# schematics.net
KiCad netlist of a schematic drawn in EAGLE
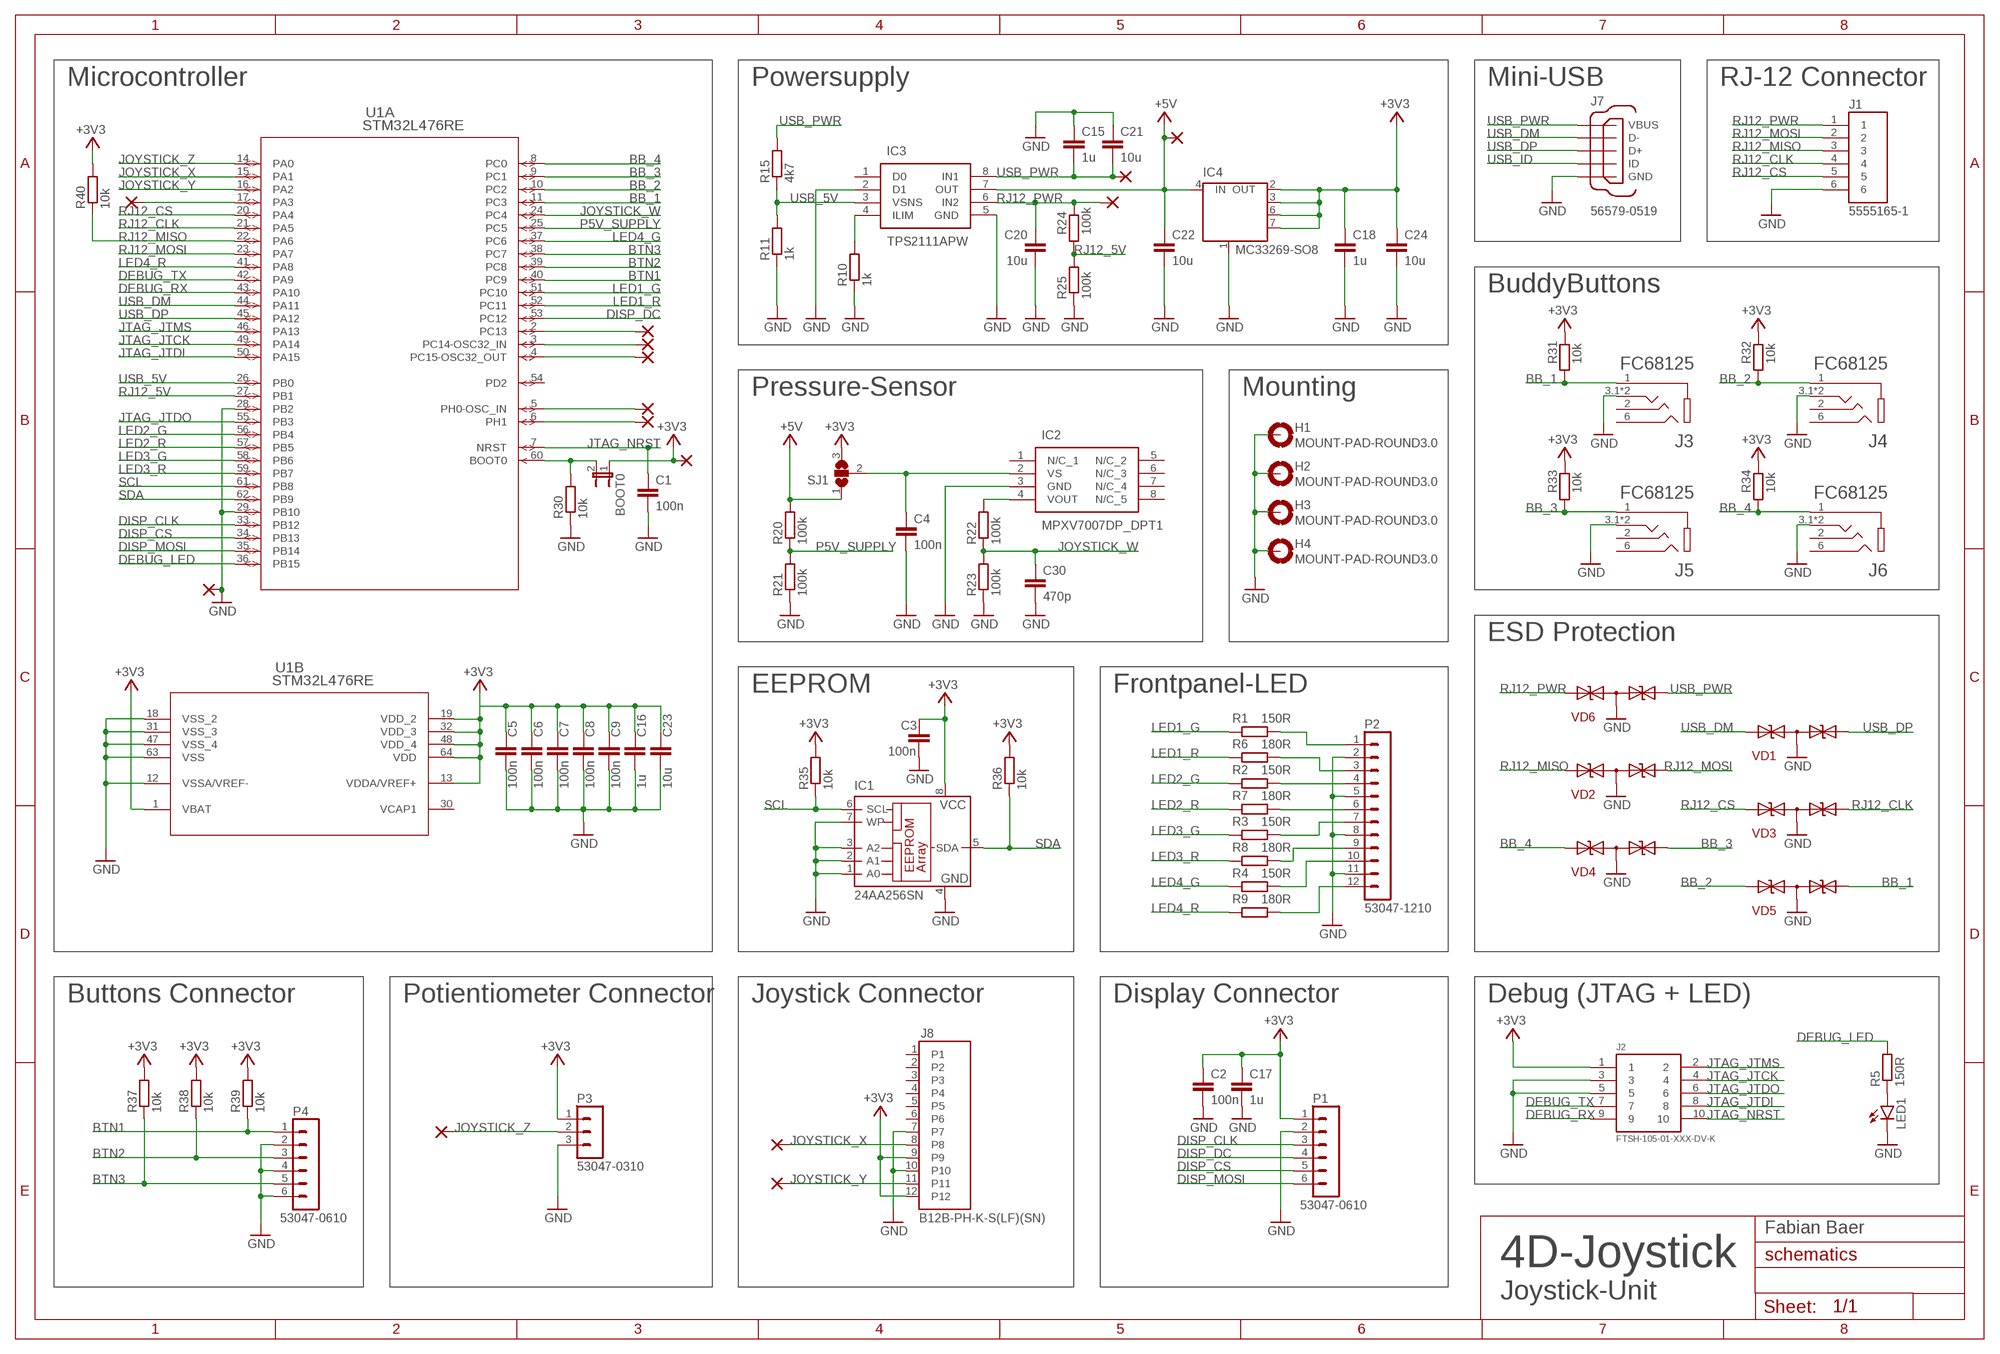
[diagram p0: schematic, sheet 1]

(export (version "E")
  (design (tool "Eeschema 10.0.6"))
  (components
    (comp (ref "BOOT0")
      (value "JP1E")
      (footprint "eagle-import:JP1")
      (libsource (lib "eagle-import") (part "JP1E"))
    )
    (comp (ref "C1")
      (value "100n")
      (footprint "eagle-import:C0603")
      (libsource (lib "eagle-import") (part "C-EUC0603"))
    )
    (comp (ref "C2")
      (value "100n")
      (footprint "eagle-import:C0603")
      (libsource (lib "eagle-import") (part "C-EUC0603"))
    )
    (comp (ref "C3")
      (value "100n")
      (footprint "eagle-import:C0603")
      (libsource (lib "eagle-import") (part "C-EUC0603"))
    )
    (comp (ref "C4")
      (value "100n")
      (footprint "eagle-import:C0603")
      (libsource (lib "eagle-import") (part "C-EUC0603"))
    )
    (comp (ref "C5")
      (value "100n")
      (footprint "eagle-import:C0603")
      (libsource (lib "eagle-import") (part "C-EUC0603"))
    )
    (comp (ref "C6")
      (value "100n")
      (footprint "eagle-import:C0603")
      (libsource (lib "eagle-import") (part "C-EUC0603"))
    )
    (comp (ref "C7")
      (value "100n")
      (footprint "eagle-import:C0603")
      (libsource (lib "eagle-import") (part "C-EUC0603"))
    )
    (comp (ref "C8")
      (value "100n")
      (footprint "eagle-import:C0603")
      (libsource (lib "eagle-import") (part "C-EUC0603"))
    )
    (comp (ref "C9")
      (value "100n")
      (footprint "eagle-import:C0603")
      (libsource (lib "eagle-import") (part "C-EUC0603"))
    )
    (comp (ref "C15")
      (value "1u")
      (footprint "eagle-import:C0603")
      (libsource (lib "eagle-import") (part "C-EUC0603"))
    )
    (comp (ref "C16")
      (value "1u")
      (footprint "eagle-import:C0603")
      (libsource (lib "eagle-import") (part "C-EUC0603"))
    )
    (comp (ref "C17")
      (value "1u")
      (footprint "eagle-import:C0603")
      (libsource (lib "eagle-import") (part "C-EUC0603"))
    )
    (comp (ref "C18")
      (value "1u")
      (footprint "eagle-import:C0603")
      (libsource (lib "eagle-import") (part "C-EUC0603"))
    )
    (comp (ref "C20")
      (value "10u")
      (footprint "eagle-import:C0603")
      (libsource (lib "eagle-import") (part "C-EUC0603"))
    )
    (comp (ref "C21")
      (value "10u")
      (footprint "eagle-import:C0603")
      (libsource (lib "eagle-import") (part "C-EUC0603"))
    )
    (comp (ref "C22")
      (value "10u")
      (footprint "eagle-import:C0603")
      (libsource (lib "eagle-import") (part "C-EUC0603"))
    )
    (comp (ref "C23")
      (value "10u")
      (footprint "eagle-import:C0603")
      (libsource (lib "eagle-import") (part "C-EUC0603"))
    )
    (comp (ref "C24")
      (value "10u")
      (footprint "eagle-import:C0603")
      (libsource (lib "eagle-import") (part "C-EUC0603"))
    )
    (comp (ref "C30")
      (value "470p")
      (footprint "eagle-import:C0603")
      (libsource (lib "eagle-import") (part "C-EUC0603"))
    )
    (comp (ref "H1")
      (value "MOUNT-PAD-ROUND3.0")
      (footprint "eagle-import:3,0-PAD")
      (libsource (lib "eagle-import") (part "MOUNT-PAD-ROUND3.0"))
    )
    (comp (ref "H2")
      (value "MOUNT-PAD-ROUND3.0")
      (footprint "eagle-import:3,0-PAD")
      (libsource (lib "eagle-import") (part "MOUNT-PAD-ROUND3.0"))
    )
    (comp (ref "H3")
      (value "MOUNT-PAD-ROUND3.0")
      (footprint "eagle-import:3,0-PAD")
      (libsource (lib "eagle-import") (part "MOUNT-PAD-ROUND3.0"))
    )
    (comp (ref "H4")
      (value "MOUNT-PAD-ROUND3.0")
      (footprint "eagle-import:3,0-PAD")
      (libsource (lib "eagle-import") (part "MOUNT-PAD-ROUND3.0"))
    )
    (comp (ref "IC1")
      (value "24AA256SN")
      (footprint "eagle-import:SO-08")
      (fields (field (name "MPN") "24AA256T-I/SM"))
      (libsource (lib "eagle-import") (part "24SNAA256"))
    )
    (comp (ref "IC2")
      (value "MPXV7007DP_DPT1")
      (footprint "eagle-import:MPXV7007DPDPT1")
      (fields (field (name "MANUFACTURER_PART_NUMBER") "MPXV7007DP/DPT1"))
      (libsource (lib "eagle-import") (part "MPXV7007DP_DPT1"))
    )
    (comp (ref "IC3")
      (value "TPS2111APW")
      (footprint "eagle-import:SOP65P640X120-8N")
      (fields (field (name "MOUSER_PART_NUMBER") "595-TPS2111APW") (field (name "RS_PART_NUMBER") "6658866P"))
      (libsource (lib "eagle-import") (part "TPS2111APW"))
    )
    (comp (ref "IC4")
      (value "MC33269-SO8")
      (footprint "eagle-import:SO08")
      (libsource (lib "eagle-import") (part "MC33269-SO8"))
    )
    (comp (ref "J1")
      (value "5555165-1")
      (footprint "eagle-import:TE_5555165-1")
      (fields (field (name "MF") "TE Connectivity"))
      (libsource (lib "eagle-import") (part "5555165-1"))
    )
    (comp (ref "J2")
      (value "FTSH-105-01-XXX-DV-K")
      (footprint "eagle-import:FTSH-105-01-XXX-DV-K")
      (libsource (lib "eagle-import") (part "FTSH-105-01-XXX-DV-K"))
    )
    (comp (ref "J3")
      (value "FC68125")
      (footprint "eagle-import:CLIFF_FC68125")
      (fields (field (name "MF") "Cliff Electronics"))
      (libsource (lib "eagle-import") (part "FC68125"))
    )
    (comp (ref "J4")
      (value "FC68125")
      (footprint "eagle-import:CLIFF_FC68125")
      (fields (field (name "MF") "Cliff Electronics"))
      (libsource (lib "eagle-import") (part "FC68125"))
    )
    (comp (ref "J5")
      (value "FC68125")
      (footprint "eagle-import:CLIFF_FC68125")
      (fields (field (name "MF") "Cliff Electronics"))
      (libsource (lib "eagle-import") (part "FC68125"))
    )
    (comp (ref "J6")
      (value "FC68125")
      (footprint "eagle-import:CLIFF_FC68125")
      (fields (field (name "MF") "Cliff Electronics"))
      (libsource (lib "eagle-import") (part "FC68125"))
    )
    (comp (ref "J7")
      (value "56579-0519")
      (footprint "eagle-import:MOLEX_56579-0519")
      (fields (field (name "MF") "Molex"))
      (libsource (lib "eagle-import") (part "56579-0519"))
    )
    (comp (ref "J8")
      (value "B12B-PH-K-S(LF)(SN)")
      (footprint "eagle-import:JST_B12B-PH-K-S(LF)(SN)")
      (fields (field (name "MF") "JST Sales") (field (name "MP") "B12B-PH-K-S_LF__SN_"))
      (libsource (lib "eagle-import") (part "B12B-PH-K-S(LF)(SN)"))
    )
    (comp (ref "LED1")
      (value "LEDSML0603")
      (footprint "eagle-import:SML0603")
      (libsource (lib "eagle-import") (part "LEDSML0603"))
    )
    (comp (ref "P1")
      (value "53047-0610")
      (footprint "eagle-import:53047-0610")
      (libsource (lib "eagle-import") (part "53047-0610"))
    )
    (comp (ref "P2")
      (value "53047-1210")
      (footprint "eagle-import:53047-1210")
      (libsource (lib "eagle-import") (part "53047-1210"))
    )
    (comp (ref "P3")
      (value "53047-0310")
      (footprint "eagle-import:53047-0310")
      (libsource (lib "eagle-import") (part "53047-0310"))
    )
    (comp (ref "P4")
      (value "53047-0610")
      (footprint "eagle-import:53047-0610")
      (libsource (lib "eagle-import") (part "53047-0610"))
    )
    (comp (ref "PAD1")
      (value "WIREPAD1,6/0,9")
      (footprint "eagle-import:1,6_0,9")
      (libsource (lib "eagle-import") (part "WIREPAD1,6/0,9"))
    )
    (comp (ref "PAD2")
      (value "WIREPAD1,6/0,9")
      (footprint "eagle-import:1,6_0,9")
      (libsource (lib "eagle-import") (part "WIREPAD1,6/0,9"))
    )
    (comp (ref "PAD3")
      (value "WIREPAD1,6/0,9")
      (footprint "eagle-import:1,6_0,9")
      (libsource (lib "eagle-import") (part "WIREPAD1,6/0,9"))
    )
    (comp (ref "PAD4")
      (value "WIREPAD1,6/0,9")
      (footprint "eagle-import:1,6_0,9")
      (libsource (lib "eagle-import") (part "WIREPAD1,6/0,9"))
    )
    (comp (ref "PAD5")
      (value "WIREPAD1,6/0,9")
      (footprint "eagle-import:1,6_0,9")
      (libsource (lib "eagle-import") (part "WIREPAD1,6/0,9"))
    )
    (comp (ref "PAD6")
      (value "WIREPAD1,6/0,9")
      (footprint "eagle-import:1,6_0,9")
      (libsource (lib "eagle-import") (part "WIREPAD1,6/0,9"))
    )
    (comp (ref "PAD7")
      (value "WIREPAD1,6/0,9")
      (footprint "eagle-import:1,6_0,9")
      (libsource (lib "eagle-import") (part "WIREPAD1,6/0,9"))
    )
    (comp (ref "PAD8")
      (value "WIREPAD1,6/0,9")
      (footprint "eagle-import:1,6_0,9")
      (libsource (lib "eagle-import") (part "WIREPAD1,6/0,9"))
    )
    (comp (ref "PAD9")
      (value "WIREPAD1,6/0,9")
      (footprint "eagle-import:1,6_0,9")
      (libsource (lib "eagle-import") (part "WIREPAD1,6/0,9"))
    )
    (comp (ref "PAD10")
      (value "WIREPAD1,6/0,9")
      (footprint "eagle-import:1,6_0,9")
      (libsource (lib "eagle-import") (part "WIREPAD1,6/0,9"))
    )
    (comp (ref "PAD11")
      (value "WIREPAD1,6/0,9")
      (footprint "eagle-import:1,6_0,9")
      (libsource (lib "eagle-import") (part "WIREPAD1,6/0,9"))
    )
    (comp (ref "PAD12")
      (value "WIREPAD1,6/0,9")
      (footprint "eagle-import:1,6_0,9")
      (libsource (lib "eagle-import") (part "WIREPAD1,6/0,9"))
    )
    (comp (ref "PAD13")
      (value "WIREPAD1,6/0,9")
      (footprint "eagle-import:1,6_0,9")
      (libsource (lib "eagle-import") (part "WIREPAD1,6/0,9"))
    )
    (comp (ref "PAD14")
      (value "WIREPAD1,6/0,9")
      (footprint "eagle-import:1,6_0,9")
      (libsource (lib "eagle-import") (part "WIREPAD1,6/0,9"))
    )
    (comp (ref "R1")
      (value "150R")
      (footprint "eagle-import:R0603")
      (libsource (lib "eagle-import") (part "R-EU_R0603"))
    )
    (comp (ref "R2")
      (value "150R")
      (footprint "eagle-import:R0603")
      (libsource (lib "eagle-import") (part "R-EU_R0603"))
    )
    (comp (ref "R3")
      (value "150R")
      (footprint "eagle-import:R0603")
      (libsource (lib "eagle-import") (part "R-EU_R0603"))
    )
    (comp (ref "R4")
      (value "150R")
      (footprint "eagle-import:R0603")
      (libsource (lib "eagle-import") (part "R-EU_R0603"))
    )
    (comp (ref "R5")
      (value "150R")
      (footprint "eagle-import:R0603")
      (libsource (lib "eagle-import") (part "R-EU_R0603"))
    )
    (comp (ref "R6")
      (value "180R")
      (footprint "eagle-import:R0603")
      (libsource (lib "eagle-import") (part "R-EU_R0603"))
    )
    (comp (ref "R7")
      (value "180R")
      (footprint "eagle-import:R0603")
      (libsource (lib "eagle-import") (part "R-EU_R0603"))
    )
    (comp (ref "R8")
      (value "180R")
      (footprint "eagle-import:R0603")
      (libsource (lib "eagle-import") (part "R-EU_R0603"))
    )
    (comp (ref "R9")
      (value "180R")
      (footprint "eagle-import:R0603")
      (libsource (lib "eagle-import") (part "R-EU_R0603"))
    )
    (comp (ref "R10")
      (value "1k")
      (footprint "eagle-import:R0603")
      (libsource (lib "eagle-import") (part "R-EU_R0603"))
    )
    (comp (ref "R11")
      (value "1k")
      (footprint "eagle-import:R0603")
      (libsource (lib "eagle-import") (part "R-EU_R0603"))
    )
    (comp (ref "R15")
      (value "4k7")
      (footprint "eagle-import:R0603")
      (libsource (lib "eagle-import") (part "R-EU_R0603"))
    )
    (comp (ref "R20")
      (value "100k")
      (footprint "eagle-import:R0603")
      (libsource (lib "eagle-import") (part "R-EU_R0603"))
    )
    (comp (ref "R21")
      (value "100k")
      (footprint "eagle-import:R0603")
      (libsource (lib "eagle-import") (part "R-EU_R0603"))
    )
    (comp (ref "R22")
      (value "100k")
      (footprint "eagle-import:R0603")
      (libsource (lib "eagle-import") (part "R-EU_R0603"))
    )
    (comp (ref "R23")
      (value "100k")
      (footprint "eagle-import:R0603")
      (libsource (lib "eagle-import") (part "R-EU_R0603"))
    )
    (comp (ref "R24")
      (value "100k")
      (footprint "eagle-import:R0603")
      (libsource (lib "eagle-import") (part "R-EU_R0603"))
    )
    (comp (ref "R25")
      (value "100k")
      (footprint "eagle-import:R0603")
      (libsource (lib "eagle-import") (part "R-EU_R0603"))
    )
    (comp (ref "R30")
      (value "10k")
      (footprint "eagle-import:R0603")
      (libsource (lib "eagle-import") (part "R-EU_R0603"))
    )
    (comp (ref "R31")
      (value "10k")
      (footprint "eagle-import:R0603")
      (libsource (lib "eagle-import") (part "R-EU_R0603"))
    )
    (comp (ref "R32")
      (value "10k")
      (footprint "eagle-import:R0603")
      (libsource (lib "eagle-import") (part "R-EU_R0603"))
    )
    (comp (ref "R33")
      (value "10k")
      (footprint "eagle-import:R0603")
      (libsource (lib "eagle-import") (part "R-EU_R0603"))
    )
    (comp (ref "R34")
      (value "10k")
      (footprint "eagle-import:R0603")
      (libsource (lib "eagle-import") (part "R-EU_R0603"))
    )
    (comp (ref "R35")
      (value "10k")
      (footprint "eagle-import:R0603")
      (libsource (lib "eagle-import") (part "R-EU_R0603"))
    )
    (comp (ref "R36")
      (value "10k")
      (footprint "eagle-import:R0603")
      (libsource (lib "eagle-import") (part "R-EU_R0603"))
    )
    (comp (ref "R37")
      (value "10k")
      (footprint "eagle-import:R0603")
      (libsource (lib "eagle-import") (part "R-EU_R0603"))
    )
    (comp (ref "R38")
      (value "10k")
      (footprint "eagle-import:R0603")
      (libsource (lib "eagle-import") (part "R-EU_R0603"))
    )
    (comp (ref "R39")
      (value "10k")
      (footprint "eagle-import:R0603")
      (libsource (lib "eagle-import") (part "R-EU_R0603"))
    )
    (comp (ref "R40")
      (value "10k")
      (footprint "eagle-import:R0603")
      (libsource (lib "eagle-import") (part "R-EU_R0603"))
    )
    (comp (ref "SJ1")
      (value "SJ2W")
      (footprint "eagle-import:SJ_2")
      (libsource (lib "eagle-import") (part "SJ2W"))
    )
    (comp (ref "U1")
      (value "STM32L476RE")
      (footprint "eagle-import:LQFP64-10X10MM")
      (fields (field (name "MANUFACTURER_PART_NUMBER") "STM32F4X1R1"))
      (libsource (lib "eagle-import") (part "STM32F4X1R1"))
    )
    (comp (ref "VD1")
      (value "PGB102ST23WR")
      (footprint "eagle-import:SOT23")
      (libsource (lib "eagle-import") (part "PGB102ST23WR"))
    )
    (comp (ref "VD2")
      (value "PGB102ST23WR")
      (footprint "eagle-import:SOT23")
      (libsource (lib "eagle-import") (part "PGB102ST23WR"))
    )
    (comp (ref "VD3")
      (value "PGB102ST23WR")
      (footprint "eagle-import:SOT23")
      (libsource (lib "eagle-import") (part "PGB102ST23WR"))
    )
    (comp (ref "VD4")
      (value "PGB102ST23WR")
      (footprint "eagle-import:SOT23")
      (libsource (lib "eagle-import") (part "PGB102ST23WR"))
    )
    (comp (ref "VD5")
      (value "PGB102ST23WR")
      (footprint "eagle-import:SOT23")
      (libsource (lib "eagle-import") (part "PGB102ST23WR"))
    )
    (comp (ref "VD6")
      (value "PGB102ST23WR")
      (footprint "eagle-import:SOT23")
      (libsource (lib "eagle-import") (part "PGB102ST23WR"))
    )
  )
  (nets
    (net (code "1") (name "+3V3") (class "Default")
      (node (ref "BOOT0") (pin "1") (pinfunction "1_1") (pintype "passive"))
      (node (ref "C16") (pin "1") (pinfunction "1_1") (pintype "passive"))
      (node (ref "C17") (pin "1") (pinfunction "1_1") (pintype "passive"))
      (node (ref "C18") (pin "1") (pinfunction "1_1") (pintype "passive"))
      (node (ref "C2") (pin "1") (pinfunction "1_1") (pintype "passive"))
      (node (ref "C23") (pin "1") (pinfunction "1_1") (pintype "passive"))
      (node (ref "C24") (pin "1") (pinfunction "1_1") (pintype "passive"))
      (node (ref "C3") (pin "1") (pinfunction "1_1") (pintype "passive"))
      (node (ref "C5") (pin "1") (pinfunction "1_1") (pintype "passive"))
      (node (ref "C6") (pin "1") (pinfunction "1_1") (pintype "passive"))
      (node (ref "C7") (pin "1") (pinfunction "1_1") (pintype "passive"))
      (node (ref "C8") (pin "1") (pinfunction "1_1") (pintype "passive"))
      (node (ref "C9") (pin "1") (pinfunction "1_1") (pintype "passive"))
      (node (ref "IC1") (pin "8") (pinfunction "VCC_8") (pintype "power_in"))
      (node (ref "IC4") (pin "2") (pinfunction "OUT_2") (pintype "passive"))
      (node (ref "IC4") (pin "3") (pinfunction "OUT_3") (pintype "passive"))
      (node (ref "IC4") (pin "6") (pinfunction "OUT_6") (pintype "passive"))
      (node (ref "IC4") (pin "7") (pinfunction "OUT_7") (pintype "passive"))
      (node (ref "J2") (pin "1") (pinfunction "1_1") (pintype "bidirectional"))
      (node (ref "J8") (pin "12") (pinfunction "P12_12") (pintype "passive"))
      (node (ref "J8") (pin "9") (pinfunction "P9_9") (pintype "passive"))
      (node (ref "P1") (pin "1") (pinfunction "1_1") (pintype "passive"))
      (node (ref "P3") (pin "1") (pinfunction "1_1") (pintype "passive"))
      (node (ref "PAD7") (pin "1") (pinfunction "P_1") (pintype "passive"))
      (node (ref "R31") (pin "2") (pinfunction "2_2") (pintype "passive"))
      (node (ref "R32") (pin "2") (pinfunction "2_2") (pintype "passive"))
      (node (ref "R33") (pin "2") (pinfunction "2_2") (pintype "passive"))
      (node (ref "R34") (pin "2") (pinfunction "2_2") (pintype "passive"))
      (node (ref "R35") (pin "2") (pinfunction "2_2") (pintype "passive"))
      (node (ref "R36") (pin "2") (pinfunction "2_2") (pintype "passive"))
      (node (ref "R37") (pin "2") (pinfunction "2_2") (pintype "passive"))
      (node (ref "R38") (pin "2") (pinfunction "2_2") (pintype "passive"))
      (node (ref "R39") (pin "2") (pinfunction "2_2") (pintype "passive"))
      (node (ref "R40") (pin "2") (pinfunction "2_2") (pintype "passive"))
      (node (ref "SJ1") (pin "3") (pinfunction "3_3") (pintype "passive"))
      (node (ref "U1") (pin "1") (pinfunction "VBAT_1") (pintype "power_in"))
      (node (ref "U1") (pin "13") (pinfunction "VDDA/VREF+_13") (pintype "power_in"))
      (node (ref "U1") (pin "19") (pinfunction "VDD_2_19") (pintype "power_in"))
      (node (ref "U1") (pin "32") (pinfunction "VDD_3_32") (pintype "power_in"))
      (node (ref "U1") (pin "48") (pinfunction "VDD_4_48") (pintype "power_in"))
      (node (ref "U1") (pin "64") (pinfunction "VDD_64") (pintype "power_in"))
    )
    (net (code "2") (name "+5V") (class "Default")
      (node (ref "C22") (pin "1") (pinfunction "1_1") (pintype "passive"))
      (node (ref "IC3") (pin "7") (pinfunction "OUT_7") (pintype "output"))
      (node (ref "IC4") (pin "4") (pinfunction "IN_4") (pintype "input"))
      (node (ref "PAD9") (pin "1") (pinfunction "P_1") (pintype "passive"))
      (node (ref "R20") (pin "2") (pinfunction "2_2") (pintype "passive"))
      (node (ref "SJ1") (pin "1") (pinfunction "1_1") (pintype "passive"))
    )
    (net (code "3") (name "/BB_1") (class "Default")
      (node (ref "J3") (pin "1") (pinfunction "1S_1") (pintype "passive"))
      (node (ref "R31") (pin "1") (pinfunction "1_1") (pintype "passive"))
      (node (ref "U1") (pin "11") (pinfunction "PC3_11") (pintype "bidirectional"))
      (node (ref "VD5") (pin "1") (pinfunction "A_1") (pintype "passive"))
    )
    (net (code "4") (name "/BB_2") (class "Default")
      (node (ref "J4") (pin "1") (pinfunction "1S_1") (pintype "passive"))
      (node (ref "R32") (pin "1") (pinfunction "1_1") (pintype "passive"))
      (node (ref "U1") (pin "10") (pinfunction "PC2_10") (pintype "bidirectional"))
      (node (ref "VD5") (pin "2") (pinfunction "A1_2") (pintype "passive"))
    )
    (net (code "5") (name "/BB_3") (class "Default")
      (node (ref "J5") (pin "1") (pinfunction "1S_1") (pintype "passive"))
      (node (ref "R33") (pin "1") (pinfunction "1_1") (pintype "passive"))
      (node (ref "U1") (pin "9") (pinfunction "PC1_9") (pintype "bidirectional"))
      (node (ref "VD4") (pin "1") (pinfunction "A_1") (pintype "passive"))
    )
    (net (code "6") (name "/BB_4") (class "Default")
      (node (ref "J6") (pin "1") (pinfunction "1S_1") (pintype "passive"))
      (node (ref "R34") (pin "1") (pinfunction "1_1") (pintype "passive"))
      (node (ref "U1") (pin "8") (pinfunction "PC0_8") (pintype "bidirectional"))
      (node (ref "VD4") (pin "2") (pinfunction "A1_2") (pintype "passive"))
    )
    (net (code "7") (name "/BTN1") (class "Default")
      (node (ref "P4") (pin "1") (pinfunction "1_1") (pintype "passive"))
      (node (ref "R39") (pin "1") (pinfunction "1_1") (pintype "passive"))
      (node (ref "U1") (pin "40") (pinfunction "PC9_40") (pintype "bidirectional"))
    )
    (net (code "8") (name "/BTN2") (class "Default")
      (node (ref "P4") (pin "3") (pinfunction "3_3") (pintype "passive"))
      (node (ref "R38") (pin "1") (pinfunction "1_1") (pintype "passive"))
      (node (ref "U1") (pin "39") (pinfunction "PC8_39") (pintype "bidirectional"))
    )
    (net (code "9") (name "/BTN3") (class "Default")
      (node (ref "P4") (pin "5") (pinfunction "5_5") (pintype "passive"))
      (node (ref "R37") (pin "1") (pinfunction "1_1") (pintype "passive"))
      (node (ref "U1") (pin "38") (pinfunction "PC7_38") (pintype "bidirectional"))
    )
    (net (code "10") (name "/DEBUG_LED") (class "Default")
      (node (ref "R5") (pin "2") (pinfunction "2_2") (pintype "passive"))
      (node (ref "U1") (pin "36") (pinfunction "PB15_36") (pintype "bidirectional"))
    )
    (net (code "11") (name "/DEBUG_RX") (class "Default")
      (node (ref "J2") (pin "9") (pinfunction "9_9") (pintype "bidirectional"))
      (node (ref "U1") (pin "43") (pinfunction "PA10_43") (pintype "bidirectional"))
    )
    (net (code "12") (name "/DEBUG_TX") (class "Default")
      (node (ref "J2") (pin "7") (pinfunction "7_7") (pintype "bidirectional"))
      (node (ref "U1") (pin "42") (pinfunction "PA9_42") (pintype "bidirectional"))
    )
    (net (code "13") (name "/DISP_CLK") (class "Default")
      (node (ref "P1") (pin "3") (pinfunction "3_3") (pintype "passive"))
      (node (ref "U1") (pin "33") (pinfunction "PB12_33") (pintype "bidirectional"))
    )
    (net (code "14") (name "/DISP_CS") (class "Default")
      (node (ref "P1") (pin "5") (pinfunction "5_5") (pintype "passive"))
      (node (ref "U1") (pin "34") (pinfunction "PB13_34") (pintype "bidirectional"))
    )
    (net (code "15") (name "/DISP_DC") (class "Default")
      (node (ref "P1") (pin "4") (pinfunction "4_4") (pintype "passive"))
      (node (ref "U1") (pin "53") (pinfunction "PC12_53") (pintype "bidirectional"))
    )
    (net (code "16") (name "/DISP_MOSI") (class "Default")
      (node (ref "P1") (pin "6") (pinfunction "6_6") (pintype "passive"))
      (node (ref "U1") (pin "35") (pinfunction "PB14_35") (pintype "bidirectional"))
    )
    (net (code "17") (name "/JOYSTICK_W") (class "Default")
      (node (ref "C30") (pin "1") (pinfunction "1_1") (pintype "passive"))
      (node (ref "R22") (pin "1") (pinfunction "1_1") (pintype "passive"))
      (node (ref "R23") (pin "2") (pinfunction "2_2") (pintype "passive"))
      (node (ref "U1") (pin "24") (pinfunction "PC4_24") (pintype "bidirectional"))
    )
    (net (code "18") (name "/JOYSTICK_X") (class "Default")
      (node (ref "J8") (pin "8") (pinfunction "P8_8") (pintype "passive"))
      (node (ref "PAD12") (pin "1") (pinfunction "P_1") (pintype "passive"))
      (node (ref "U1") (pin "15") (pinfunction "PA1_15") (pintype "bidirectional"))
    )
    (net (code "19") (name "/JOYSTICK_Y") (class "Default")
      (node (ref "J8") (pin "11") (pinfunction "P11_11") (pintype "passive"))
      (node (ref "PAD13") (pin "1") (pinfunction "P_1") (pintype "passive"))
      (node (ref "U1") (pin "16") (pinfunction "PA2_16") (pintype "bidirectional"))
    )
    (net (code "20") (name "/JOYSTICK_Z") (class "Default")
      (node (ref "P3") (pin "2") (pinfunction "2_2") (pintype "passive"))
      (node (ref "PAD14") (pin "1") (pinfunction "P_1") (pintype "passive"))
      (node (ref "U1") (pin "14") (pinfunction "PA0_14") (pintype "bidirectional"))
    )
    (net (code "21") (name "/JTAG_JTCK") (class "Default")
      (node (ref "J2") (pin "4") (pinfunction "4_4") (pintype "bidirectional"))
      (node (ref "U1") (pin "49") (pinfunction "PA14_49") (pintype "bidirectional"))
    )
    (net (code "22") (name "/JTAG_JTDI") (class "Default")
      (node (ref "J2") (pin "8") (pinfunction "8_8") (pintype "bidirectional"))
      (node (ref "U1") (pin "50") (pinfunction "PA15_50") (pintype "bidirectional"))
    )
    (net (code "23") (name "/JTAG_JTDO") (class "Default")
      (node (ref "J2") (pin "6") (pinfunction "6_6") (pintype "bidirectional"))
      (node (ref "U1") (pin "55") (pinfunction "PB3_55") (pintype "bidirectional"))
    )
    (net (code "24") (name "/JTAG_JTMS") (class "Default")
      (node (ref "J2") (pin "2") (pinfunction "2_2") (pintype "bidirectional"))
      (node (ref "U1") (pin "46") (pinfunction "PA13_46") (pintype "bidirectional"))
    )
    (net (code "25") (name "/JTAG_NRST") (class "Default")
      (node (ref "C1") (pin "1") (pinfunction "1_1") (pintype "passive"))
      (node (ref "J2") (pin "10") (pinfunction "10_10") (pintype "bidirectional"))
      (node (ref "U1") (pin "7") (pinfunction "NRST_7") (pintype "bidirectional"))
    )
    (net (code "26") (name "/LED1_G") (class "Default")
      (node (ref "R1") (pin "2") (pinfunction "2_2") (pintype "passive"))
      (node (ref "U1") (pin "51") (pinfunction "PC10_51") (pintype "bidirectional"))
    )
    (net (code "27") (name "/LED1_R") (class "Default")
      (node (ref "R6") (pin "2") (pinfunction "2_2") (pintype "passive"))
      (node (ref "U1") (pin "52") (pinfunction "PC11_52") (pintype "bidirectional"))
    )
    (net (code "28") (name "/LED2_G") (class "Default")
      (node (ref "R2") (pin "2") (pinfunction "2_2") (pintype "passive"))
      (node (ref "U1") (pin "56") (pinfunction "PB4_56") (pintype "bidirectional"))
    )
    (net (code "29") (name "/LED2_R") (class "Default")
      (node (ref "R7") (pin "2") (pinfunction "2_2") (pintype "passive"))
      (node (ref "U1") (pin "57") (pinfunction "PB5_57") (pintype "bidirectional"))
    )
    (net (code "30") (name "/LED3_G") (class "Default")
      (node (ref "R3") (pin "2") (pinfunction "2_2") (pintype "passive"))
      (node (ref "U1") (pin "58") (pinfunction "PB6_58") (pintype "bidirectional"))
    )
    (net (code "31") (name "/LED3_R") (class "Default")
      (node (ref "R8") (pin "2") (pinfunction "2_2") (pintype "passive"))
      (node (ref "U1") (pin "59") (pinfunction "PB7_59") (pintype "bidirectional"))
    )
    (net (code "32") (name "/LED4_G") (class "Default")
      (node (ref "R4") (pin "2") (pinfunction "2_2") (pintype "passive"))
      (node (ref "U1") (pin "37") (pinfunction "PC6_37") (pintype "bidirectional"))
    )
    (net (code "33") (name "/LED4_R") (class "Default")
      (node (ref "R9") (pin "2") (pinfunction "2_2") (pintype "passive"))
      (node (ref "U1") (pin "41") (pinfunction "PA8_41") (pintype "bidirectional"))
    )
    (net (code "34") (name "/P5V_SUPPLY") (class "Default")
      (node (ref "R20") (pin "1") (pinfunction "1_1") (pintype "passive"))
      (node (ref "R21") (pin "2") (pinfunction "2_2") (pintype "passive"))
      (node (ref "U1") (pin "25") (pinfunction "PC5_25") (pintype "bidirectional"))
    )
    (net (code "35") (name "/RJ12_5V") (class "Default")
      (node (ref "R24") (pin "1") (pinfunction "1_1") (pintype "passive"))
      (node (ref "R25") (pin "2") (pinfunction "2_2") (pintype "passive"))
      (node (ref "U1") (pin "27") (pinfunction "PB1_27") (pintype "bidirectional"))
    )
    (net (code "36") (name "/RJ12_CLK") (class "Default")
      (node (ref "J1") (pin "4") (pinfunction "4_4") (pintype "passive"))
      (node (ref "U1") (pin "21") (pinfunction "PA5_21") (pintype "bidirectional"))
      (node (ref "VD3") (pin "1") (pinfunction "A_1") (pintype "passive"))
    )
    (net (code "37") (name "/RJ12_CS") (class "Default")
      (node (ref "J1") (pin "5") (pinfunction "5_5") (pintype "passive"))
      (node (ref "U1") (pin "20") (pinfunction "PA4_20") (pintype "bidirectional"))
      (node (ref "VD3") (pin "2") (pinfunction "A1_2") (pintype "passive"))
    )
    (net (code "38") (name "/RJ12_MISO") (class "Default")
      (node (ref "J1") (pin "3") (pinfunction "3_3") (pintype "passive"))
      (node (ref "R40") (pin "1") (pinfunction "1_1") (pintype "passive"))
      (node (ref "U1") (pin "22") (pinfunction "PA6_22") (pintype "bidirectional"))
      (node (ref "VD2") (pin "2") (pinfunction "A1_2") (pintype "passive"))
    )
    (net (code "39") (name "/RJ12_MOSI") (class "Default")
      (node (ref "J1") (pin "2") (pinfunction "2_2") (pintype "passive"))
      (node (ref "U1") (pin "23") (pinfunction "PA7_23") (pintype "bidirectional"))
      (node (ref "VD2") (pin "1") (pinfunction "A_1") (pintype "passive"))
    )
    (net (code "40") (name "/RJ12_PWR") (class "Default")
      (node (ref "C20") (pin "1") (pinfunction "1_1") (pintype "passive"))
      (node (ref "IC3") (pin "6") (pinfunction "IN2_6") (pintype "input"))
      (node (ref "J1") (pin "1") (pinfunction "1_1") (pintype "passive"))
      (node (ref "PAD11") (pin "1") (pinfunction "P_1") (pintype "passive"))
      (node (ref "R24") (pin "2") (pinfunction "2_2") (pintype "passive"))
      (node (ref "VD6") (pin "2") (pinfunction "A1_2") (pintype "passive"))
    )
    (net (code "41") (name "/SCL") (class "Default")
      (node (ref "IC1") (pin "6") (pinfunction "SCL_6") (pintype "input"))
      (node (ref "R35") (pin "1") (pinfunction "1_1") (pintype "passive"))
      (node (ref "U1") (pin "61") (pinfunction "PB8_61") (pintype "bidirectional"))
    )
    (net (code "42") (name "/SDA") (class "Default")
      (node (ref "IC1") (pin "5") (pinfunction "SDA_5") (pintype "bidirectional"))
      (node (ref "R36") (pin "1") (pinfunction "1_1") (pintype "passive"))
      (node (ref "U1") (pin "62") (pinfunction "PB9_62") (pintype "bidirectional"))
    )
    (net (code "43") (name "/USB_5V") (class "Default")
      (node (ref "IC3") (pin "3") (pinfunction "VSNS_3") (pintype "input"))
      (node (ref "R11") (pin "2") (pinfunction "2_2") (pintype "passive"))
      (node (ref "R15") (pin "1") (pinfunction "1_1") (pintype "passive"))
      (node (ref "U1") (pin "26") (pinfunction "PB0_26") (pintype "bidirectional"))
    )
    (net (code "44") (name "/USB_DM") (class "Default")
      (node (ref "J7") (pin "2") (pinfunction "D-_2") (pintype "bidirectional"))
      (node (ref "U1") (pin "44") (pinfunction "PA11_44") (pintype "bidirectional"))
      (node (ref "VD1") (pin "2") (pinfunction "A1_2") (pintype "passive"))
    )
    (net (code "45") (name "/USB_DP") (class "Default")
      (node (ref "J7") (pin "3") (pinfunction "D+_3") (pintype "bidirectional"))
      (node (ref "U1") (pin "45") (pinfunction "PA12_45") (pintype "bidirectional"))
      (node (ref "VD1") (pin "1") (pinfunction "A_1") (pintype "passive"))
    )
    (net (code "46") (name "/USB_ID") (class "Default")
      (node (ref "J7") (pin "4") (pinfunction "ID_4") (pintype "bidirectional"))
    )
    (net (code "47") (name "/USB_PWR") (class "Default")
      (node (ref "C15") (pin "2") (pinfunction "2_2") (pintype "passive"))
      (node (ref "C21") (pin "2") (pinfunction "2_2") (pintype "passive"))
      (node (ref "IC3") (pin "8") (pinfunction "IN1_8") (pintype "input"))
      (node (ref "J7") (pin "1") (pinfunction "VBUS_1") (pintype "power_in"))
      (node (ref "PAD10") (pin "1") (pinfunction "P_1") (pintype "passive"))
      (node (ref "R15") (pin "2") (pinfunction "2_2") (pintype "passive"))
      (node (ref "VD6") (pin "1") (pinfunction "A_1") (pintype "passive"))
    )
    (net (code "48") (name "/VCAP1") (class "Default")
      (node (ref "U1") (pin "30") (pinfunction "VCAP1_30") (pintype "power_in"))
    )
    (net (code "49") (name "GND") (class "Default")
      (node (ref "C1") (pin "2") (pinfunction "2_2") (pintype "passive"))
      (node (ref "C15") (pin "1") (pinfunction "1_1") (pintype "passive"))
      (node (ref "C16") (pin "2") (pinfunction "2_2") (pintype "passive"))
      (node (ref "C17") (pin "2") (pinfunction "2_2") (pintype "passive"))
      (node (ref "C18") (pin "2") (pinfunction "2_2") (pintype "passive"))
      (node (ref "C2") (pin "2") (pinfunction "2_2") (pintype "passive"))
      (node (ref "C20") (pin "2") (pinfunction "2_2") (pintype "passive"))
      (node (ref "C21") (pin "1") (pinfunction "1_1") (pintype "passive"))
      (node (ref "C22") (pin "2") (pinfunction "2_2") (pintype "passive"))
      (node (ref "C23") (pin "2") (pinfunction "2_2") (pintype "passive"))
      (node (ref "C24") (pin "2") (pinfunction "2_2") (pintype "passive"))
      (node (ref "C3") (pin "2") (pinfunction "2_2") (pintype "passive"))
      (node (ref "C30") (pin "2") (pinfunction "2_2") (pintype "passive"))
      (node (ref "C4") (pin "2") (pinfunction "2_2") (pintype "passive"))
      (node (ref "C5") (pin "2") (pinfunction "2_2") (pintype "passive"))
      (node (ref "C6") (pin "2") (pinfunction "2_2") (pintype "passive"))
      (node (ref "C7") (pin "2") (pinfunction "2_2") (pintype "passive"))
      (node (ref "C8") (pin "2") (pinfunction "2_2") (pintype "passive"))
      (node (ref "C9") (pin "2") (pinfunction "2_2") (pintype "passive"))
      (node (ref "H1") (pin "B3,0") (pinfunction "MOUNT_B3,0") (pintype "passive"))
      (node (ref "H2") (pin "B3,0") (pinfunction "MOUNT_B3,0") (pintype "passive"))
      (node (ref "H3") (pin "B3,0") (pinfunction "MOUNT_B3,0") (pintype "passive"))
      (node (ref "H4") (pin "B3,0") (pinfunction "MOUNT_B3,0") (pintype "passive"))
      (node (ref "IC1") (pin "1") (pinfunction "A0_1") (pintype "input"))
      (node (ref "IC1") (pin "2") (pinfunction "A1_2") (pintype "input"))
      (node (ref "IC1") (pin "3") (pinfunction "A2_3") (pintype "input"))
      (node (ref "IC1") (pin "4") (pinfunction "GND_4") (pintype "power_in"))
      (node (ref "IC1") (pin "7") (pinfunction "WP_7") (pintype "input"))
      (node (ref "IC2") (pin "3") (pinfunction "GND_3") (pintype "bidirectional"))
      (node (ref "IC3") (pin "2") (pinfunction "D1_2") (pintype "input"))
      (node (ref "IC3") (pin "5") (pinfunction "GND_5") (pintype "power_in"))
      (node (ref "IC4") (pin "1") (pinfunction "GND/ADJ_1") (pintype "input"))
      (node (ref "J1") (pin "6") (pinfunction "6_6") (pintype "passive"))
      (node (ref "J2") (pin "3") (pinfunction "3_3") (pintype "bidirectional"))
      (node (ref "J2") (pin "5") (pinfunction "5_5") (pintype "bidirectional"))
      (node (ref "J3") (pin "3.1") (pinfunction "3T_3.1") (pintype "passive"))
      (node (ref "J3") (pin "3.2") (pinfunction "3T_3.2") (pintype "passive"))
      (node (ref "J4") (pin "3.1") (pinfunction "3T_3.1") (pintype "passive"))
      (node (ref "J4") (pin "3.2") (pinfunction "3T_3.2") (pintype "passive"))
      (node (ref "J5") (pin "3.1") (pinfunction "3T_3.1") (pintype "passive"))
      (node (ref "J5") (pin "3.2") (pinfunction "3T_3.2") (pintype "passive"))
      (node (ref "J6") (pin "3.1") (pinfunction "3T_3.1") (pintype "passive"))
      (node (ref "J6") (pin "3.2") (pinfunction "3T_3.2") (pintype "passive"))
      (node (ref "J7") (pin "5") (pinfunction "GND_5") (pintype "power_in"))
      (node (ref "J8") (pin "10") (pinfunction "P10_10") (pintype "passive"))
      (node (ref "J8") (pin "7") (pinfunction "P7_7") (pintype "passive"))
      (node (ref "LED1") (pin "C") (pinfunction "C_C") (pintype "passive"))
      (node (ref "P1") (pin "2") (pinfunction "2_2") (pintype "passive"))
      (node (ref "P2") (pin "11") (pinfunction "11_11") (pintype "passive"))
      (node (ref "P2") (pin "2") (pinfunction "2_2") (pintype "passive"))
      (node (ref "P2") (pin "5") (pinfunction "5_5") (pintype "passive"))
      (node (ref "P2") (pin "8") (pinfunction "8_8") (pintype "passive"))
      (node (ref "P3") (pin "3") (pinfunction "3_3") (pintype "passive"))
      (node (ref "P4") (pin "2") (pinfunction "2_2") (pintype "passive"))
      (node (ref "P4") (pin "4") (pinfunction "4_4") (pintype "passive"))
      (node (ref "P4") (pin "6") (pinfunction "6_6") (pintype "passive"))
      (node (ref "PAD8") (pin "1") (pinfunction "P_1") (pintype "passive"))
      (node (ref "R10") (pin "1") (pinfunction "1_1") (pintype "passive"))
      (node (ref "R11") (pin "1") (pinfunction "1_1") (pintype "passive"))
      (node (ref "R21") (pin "1") (pinfunction "1_1") (pintype "passive"))
      (node (ref "R23") (pin "1") (pinfunction "1_1") (pintype "passive"))
      (node (ref "R25") (pin "1") (pinfunction "1_1") (pintype "passive"))
      (node (ref "R30") (pin "1") (pinfunction "1_1") (pintype "passive"))
      (node (ref "U1") (pin "12") (pinfunction "VSSA/VREF-_12") (pintype "power_in"))
      (node (ref "U1") (pin "18") (pinfunction "VSS_2_18") (pintype "power_in"))
      (node (ref "U1") (pin "28") (pinfunction "PB2_28") (pintype "bidirectional"))
      (node (ref "U1") (pin "29") (pinfunction "PB10_29") (pintype "bidirectional"))
      (node (ref "U1") (pin "31") (pinfunction "VSS_3_31") (pintype "power_in"))
      (node (ref "U1") (pin "47") (pinfunction "VSS_4_47") (pintype "power_in"))
      (node (ref "U1") (pin "63") (pinfunction "VSS_63") (pintype "power_in"))
      (node (ref "VD1") (pin "3") (pinfunction "C_3") (pintype "passive"))
      (node (ref "VD2") (pin "3") (pinfunction "C_3") (pintype "passive"))
      (node (ref "VD3") (pin "3") (pinfunction "C_3") (pintype "passive"))
      (node (ref "VD4") (pin "3") (pinfunction "C_3") (pintype "passive"))
      (node (ref "VD5") (pin "3") (pinfunction "C_3") (pintype "passive"))
      (node (ref "VD6") (pin "3") (pinfunction "C_3") (pintype "passive"))
    )
    (net (code "50") (name "Net-(IC2-VOUT)") (class "Default")
      (node (ref "IC2") (pin "4") (pinfunction "VOUT_4") (pintype "bidirectional"))
      (node (ref "R22") (pin "2") (pinfunction "2_2") (pintype "passive"))
    )
    (net (code "51") (name "Net-(IC2-VS)") (class "Default")
      (node (ref "C4") (pin "1") (pinfunction "1_1") (pintype "passive"))
      (node (ref "IC2") (pin "2") (pinfunction "VS_2") (pintype "bidirectional"))
      (node (ref "SJ1") (pin "2") (pinfunction "2_2") (pintype "passive"))
    )
    (net (code "52") (name "Net-(IC3-ILIM)") (class "Default")
      (node (ref "IC3") (pin "4") (pinfunction "ILIM_4") (pintype "input"))
      (node (ref "R10") (pin "2") (pinfunction "2_2") (pintype "passive"))
    )
    (net (code "53") (name "Net-(LED1-PadA)") (class "Default")
      (node (ref "LED1") (pin "A") (pinfunction "A_A") (pintype "passive"))
      (node (ref "R5") (pin "1") (pinfunction "1_1") (pintype "passive"))
    )
    (net (code "54") (name "Net-(P2-Pad1)") (class "Default")
      (node (ref "P2") (pin "1") (pinfunction "1_1") (pintype "passive"))
      (node (ref "R1") (pin "1") (pinfunction "1_1") (pintype "passive"))
    )
    (net (code "55") (name "Net-(P2-Pad3)") (class "Default")
      (node (ref "P2") (pin "3") (pinfunction "3_3") (pintype "passive"))
      (node (ref "R6") (pin "1") (pinfunction "1_1") (pintype "passive"))
    )
    (net (code "56") (name "Net-(P2-Pad4)") (class "Default")
      (node (ref "P2") (pin "4") (pinfunction "4_4") (pintype "passive"))
      (node (ref "R2") (pin "1") (pinfunction "1_1") (pintype "passive"))
    )
    (net (code "57") (name "Net-(P2-Pad6)") (class "Default")
      (node (ref "P2") (pin "6") (pinfunction "6_6") (pintype "passive"))
      (node (ref "R7") (pin "1") (pinfunction "1_1") (pintype "passive"))
    )
    (net (code "58") (name "Net-(P2-Pad7)") (class "Default")
      (node (ref "P2") (pin "7") (pinfunction "7_7") (pintype "passive"))
      (node (ref "R3") (pin "1") (pinfunction "1_1") (pintype "passive"))
    )
    (net (code "59") (name "Net-(P2-Pad9)") (class "Default")
      (node (ref "P2") (pin "9") (pinfunction "9_9") (pintype "passive"))
      (node (ref "R8") (pin "1") (pinfunction "1_1") (pintype "passive"))
    )
    (net (code "60") (name "Net-(P2-Pad10)") (class "Default")
      (node (ref "P2") (pin "10") (pinfunction "10_10") (pintype "passive"))
      (node (ref "R4") (pin "1") (pinfunction "1_1") (pintype "passive"))
    )
    (net (code "61") (name "Net-(P2-Pad12)") (class "Default")
      (node (ref "P2") (pin "12") (pinfunction "12_12") (pintype "passive"))
      (node (ref "R9") (pin "1") (pinfunction "1_1") (pintype "passive"))
    )
    (net (code "62") (name "Net-(PAD1-P)") (class "Default")
      (node (ref "PAD1") (pin "1") (pinfunction "P_1") (pintype "passive"))
      (node (ref "U1") (pin "6") (pinfunction "PH1_6") (pintype "bidirectional"))
    )
    (net (code "63") (name "Net-(PAD2-P)") (class "Default")
      (node (ref "PAD2") (pin "1") (pinfunction "P_1") (pintype "passive"))
      (node (ref "U1") (pin "5") (pinfunction "PH0-OSC_IN_5") (pintype "bidirectional"))
    )
    (net (code "64") (name "Net-(PAD3-P)") (class "Default")
      (node (ref "PAD3") (pin "1") (pinfunction "P_1") (pintype "passive"))
      (node (ref "U1") (pin "2") (pinfunction "PC13_2") (pintype "bidirectional"))
    )
    (net (code "65") (name "Net-(PAD4-P)") (class "Default")
      (node (ref "PAD4") (pin "1") (pinfunction "P_1") (pintype "passive"))
      (node (ref "U1") (pin "3") (pinfunction "PC14-OSC32_IN_3") (pintype "bidirectional"))
    )
    (net (code "66") (name "Net-(PAD5-P)") (class "Default")
      (node (ref "PAD5") (pin "1") (pinfunction "P_1") (pintype "passive"))
      (node (ref "U1") (pin "4") (pinfunction "PC15-OSC32_OUT_4") (pintype "bidirectional"))
    )
    (net (code "67") (name "Net-(PAD6-P)") (class "Default")
      (node (ref "PAD6") (pin "1") (pinfunction "P_1") (pintype "passive"))
      (node (ref "U1") (pin "17") (pinfunction "PA3_17") (pintype "bidirectional"))
    )
    (net (code "68") (name "Net-(U1A-BOOT0)") (class "Default")
      (node (ref "BOOT0") (pin "2") (pinfunction "2_2") (pintype "passive"))
      (node (ref "R30") (pin "2") (pinfunction "2_2") (pintype "passive"))
      (node (ref "U1") (pin "60") (pinfunction "BOOT0_60") (pintype "input"))
    )
    (net (code "69") (name "unconnected-(IC2-N{slash}C_1-Pad1)") (class "Default")
      (node (ref "IC2") (pin "1") (pinfunction "N/C_1_1") (pintype "bidirectional"))
    )
    (net (code "70") (name "unconnected-(IC2-N{slash}C_2-Pad5)") (class "Default")
      (node (ref "IC2") (pin "5") (pinfunction "N/C_2_5") (pintype "bidirectional"))
    )
    (net (code "71") (name "unconnected-(IC2-N{slash}C_3-Pad6)") (class "Default")
      (node (ref "IC2") (pin "6") (pinfunction "N/C_3_6") (pintype "bidirectional"))
    )
    (net (code "72") (name "unconnected-(IC2-N{slash}C_4-Pad7)") (class "Default")
      (node (ref "IC2") (pin "7") (pinfunction "N/C_4_7") (pintype "bidirectional"))
    )
    (net (code "73") (name "unconnected-(IC2-N{slash}C_5-Pad8)") (class "Default")
      (node (ref "IC2") (pin "8") (pinfunction "N/C_5_8") (pintype "bidirectional"))
    )
    (net (code "74") (name "unconnected-(IC3-D0-Pad1)") (class "Default")
      (node (ref "IC3") (pin "1") (pinfunction "D0_1") (pintype "input"))
    )
    (net (code "75") (name "unconnected-(J3-2R-Pad2)") (class "Default")
      (node (ref "J3") (pin "2") (pinfunction "2R_2") (pintype "passive"))
    )
    (net (code "76") (name "unconnected-(J3-6SR-Pad6)") (class "Default")
      (node (ref "J3") (pin "6") (pinfunction "6SR_6") (pintype "passive"))
    )
    (net (code "77") (name "unconnected-(J4-2R-Pad2)") (class "Default")
      (node (ref "J4") (pin "2") (pinfunction "2R_2") (pintype "passive"))
    )
    (net (code "78") (name "unconnected-(J4-6SR-Pad6)") (class "Default")
      (node (ref "J4") (pin "6") (pinfunction "6SR_6") (pintype "passive"))
    )
    (net (code "79") (name "unconnected-(J5-2R-Pad2)") (class "Default")
      (node (ref "J5") (pin "2") (pinfunction "2R_2") (pintype "passive"))
    )
    (net (code "80") (name "unconnected-(J5-6SR-Pad6)") (class "Default")
      (node (ref "J5") (pin "6") (pinfunction "6SR_6") (pintype "passive"))
    )
    (net (code "81") (name "unconnected-(J6-2R-Pad2)") (class "Default")
      (node (ref "J6") (pin "2") (pinfunction "2R_2") (pintype "passive"))
    )
    (net (code "82") (name "unconnected-(J6-6SR-Pad6)") (class "Default")
      (node (ref "J6") (pin "6") (pinfunction "6SR_6") (pintype "passive"))
    )
    (net (code "83") (name "unconnected-(J8-P1-Pad1)") (class "Default")
      (node (ref "J8") (pin "1") (pinfunction "P1_1") (pintype "passive"))
    )
    (net (code "84") (name "unconnected-(J8-P2-Pad2)") (class "Default")
      (node (ref "J8") (pin "2") (pinfunction "P2_2") (pintype "passive"))
    )
    (net (code "85") (name "unconnected-(J8-P3-Pad3)") (class "Default")
      (node (ref "J8") (pin "3") (pinfunction "P3_3") (pintype "passive"))
    )
    (net (code "86") (name "unconnected-(J8-P4-Pad4)") (class "Default")
      (node (ref "J8") (pin "4") (pinfunction "P4_4") (pintype "passive"))
    )
    (net (code "87") (name "unconnected-(J8-P5-Pad5)") (class "Default")
      (node (ref "J8") (pin "5") (pinfunction "P5_5") (pintype "passive"))
    )
    (net (code "88") (name "unconnected-(J8-P6-Pad6)") (class "Default")
      (node (ref "J8") (pin "6") (pinfunction "P6_6") (pintype "passive"))
    )
    (net (code "89") (name "unconnected-(U1A-PD2-Pad54)") (class "Default")
      (node (ref "U1") (pin "54") (pinfunction "PD2_54") (pintype "bidirectional"))
    )
  )
)
